# Phase_Shifting_Stage.net
KiCad netlist of a schematic drawn in Altium Designer
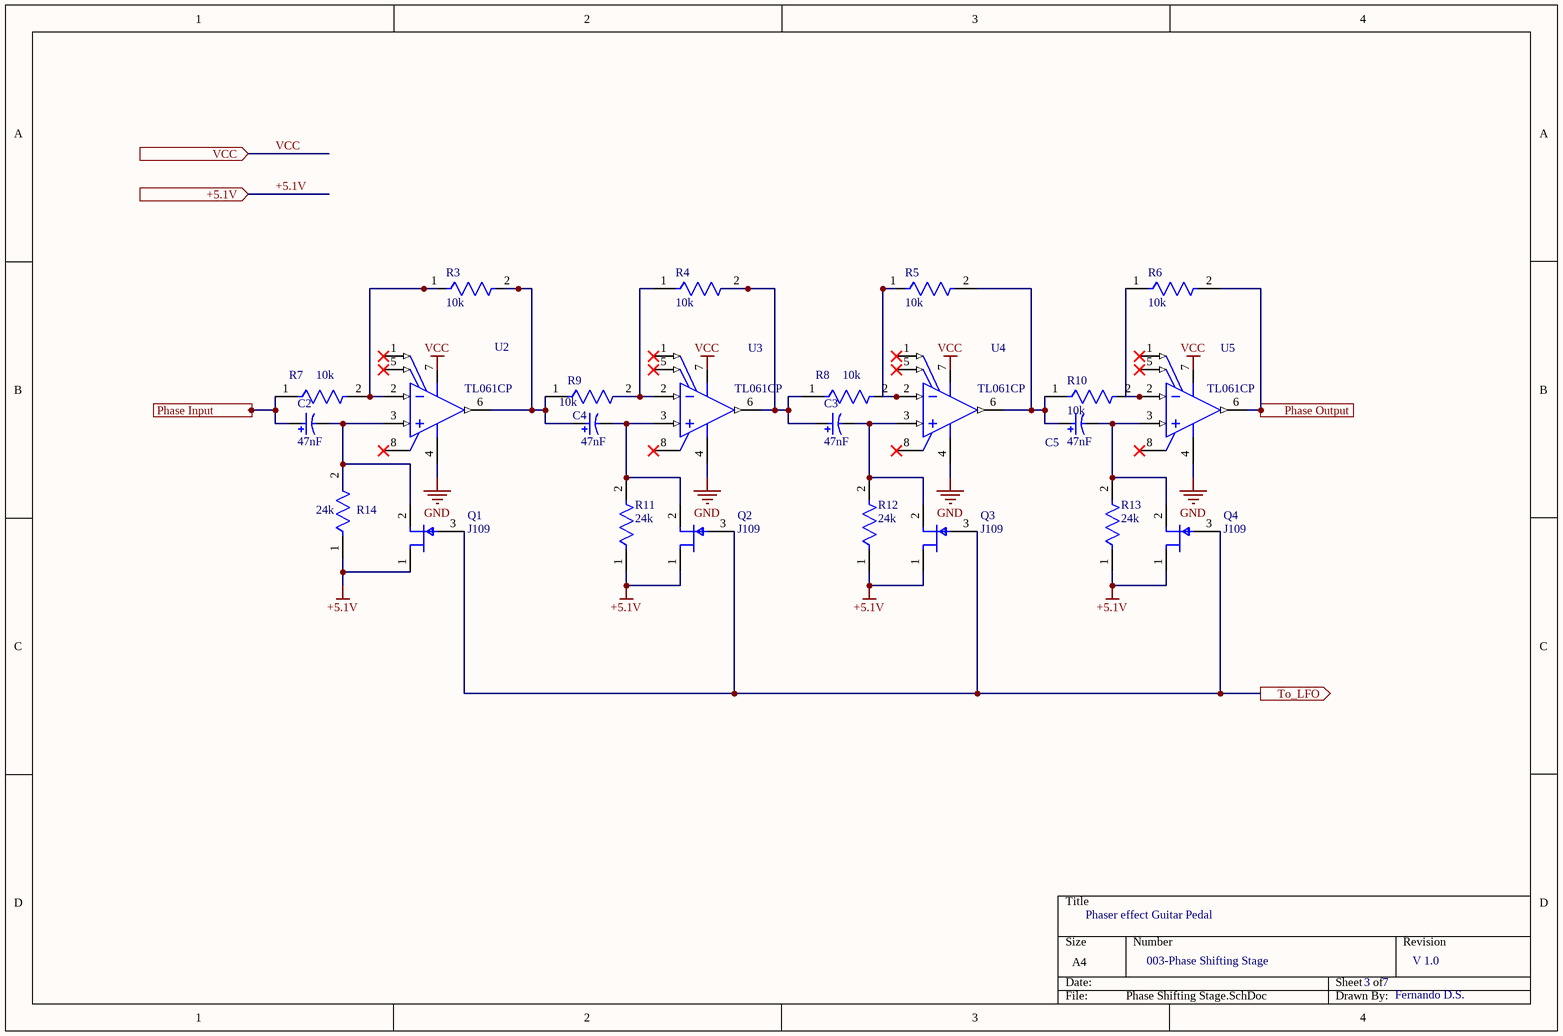
[diagram p0: Phase Shifting Stage.SchDoc]

(export (version "E")
  (design (tool "Eeschema 10.0.6"))
  (components
    (comp (ref "C2")
      (value "47nF")
      (footprint "NIC-PLF-10x13-2_V")
      (description "Aluminum Electrolytic Capacitor, 470 uF +/-20%, 10 V, -55 to 105 degC, 2-Pin THD, RoHS")
      (fields (field (name "MANUFACTURER") "Nichicon") (field (name "PARTNUMBER") "PLF1A471MDO1"))
      (libsource (lib "Altium Content Vault") (part "NIC-CAP-P-2"))
    )
    (comp (ref "C3")
      (value "47nF")
      (footprint "NIC-PLF-10x13-2_V")
      (description "Aluminum Electrolytic Capacitor, 470 uF +/-20%, 10 V, -55 to 105 degC, 2-Pin THD, RoHS")
      (fields (field (name "MANUFACTURER") "Nichicon") (field (name "PARTNUMBER") "PLF1A471MDO1"))
      (libsource (lib "Altium Content Vault") (part "NIC-CAP-P-2"))
    )
    (comp (ref "C4")
      (value "47nF")
      (footprint "NIC-PLF-10x13-2_V")
      (description "Aluminum Electrolytic Capacitor, 470 uF +/-20%, 10 V, -55 to 105 degC, 2-Pin THD, RoHS")
      (fields (field (name "MANUFACTURER") "Nichicon") (field (name "PARTNUMBER") "PLF1A471MDO1"))
      (libsource (lib "Altium Content Vault") (part "NIC-CAP-P-2"))
    )
    (comp (ref "C5")
      (value "47nF")
      (footprint "NIC-PLF-10x13-2_V")
      (description "Aluminum Electrolytic Capacitor, 470 uF +/-20%, 10 V, -55 to 105 degC, 2-Pin THD, RoHS")
      (fields (field (name "MANUFACTURER") "Nichicon") (field (name "PARTNUMBER") "PLF1A471MDO1"))
      (libsource (lib "Altium Content Vault") (part "NIC-CAP-P-2"))
    )
    (comp (ref "Q1")
      (value "J109")
      (footprint "FP-135AN-MFG")
      (description "J109 Fairchild Semiconductor J109JFET Transistor, Jfet, -25 V, 40 Ma, 6 V, TO-92, Jfet")
      (libsource (lib "Altium Content Vault") (part "14398f7355be6f33287877db3ee21c7"))
    )
    (comp (ref "Q2")
      (value "J109")
      (footprint "FP-135AN-MFG")
      (description "J109 Fairchild Semiconductor J109JFET Transistor, Jfet, -25 V, 40 Ma, 6 V, TO-92, Jfet")
      (libsource (lib "Altium Content Vault") (part "14398f7355be6f33287877db3ee21c7"))
    )
    (comp (ref "Q3")
      (value "J109")
      (footprint "FP-135AN-MFG")
      (description "J109 Fairchild Semiconductor J109JFET Transistor, Jfet, -25 V, 40 Ma, 6 V, TO-92, Jfet")
      (libsource (lib "Altium Content Vault") (part "14398f7355be6f33287877db3ee21c7"))
    )
    (comp (ref "Q4")
      (value "J109")
      (footprint "FP-135AN-MFG")
      (description "J109 Fairchild Semiconductor J109JFET Transistor, Jfet, -25 V, 40 Ma, 6 V, TO-92, Jfet")
      (libsource (lib "Altium Content Vault") (part "14398f7355be6f33287877db3ee21c7"))
    )
    (comp (ref "R3")
      (value "10k")
      (footprint "FP-MRS25-MFG")
      (fields (field (name "TOLERANCE") "1%"))
      (libsource (lib "Altium Content Vault") (part "1029c3af85768c4190bb7ad29bc67b5"))
    )
    (comp (ref "R4")
      (value "10k")
      (footprint "FP-MRS25-MFG")
      (fields (field (name "TOLERANCE") "1%"))
      (libsource (lib "Altium Content Vault") (part "1029c3af85768c4190bb7ad29bc67b5"))
    )
    (comp (ref "R5")
      (value "10k")
      (footprint "FP-MRS25-MFG")
      (fields (field (name "TOLERANCE") "1%"))
      (libsource (lib "Altium Content Vault") (part "1029c3af85768c4190bb7ad29bc67b5"))
    )
    (comp (ref "R6")
      (value "10k")
      (footprint "FP-MRS25-MFG")
      (fields (field (name "TOLERANCE") "1%"))
      (libsource (lib "Altium Content Vault") (part "1029c3af85768c4190bb7ad29bc67b5"))
    )
    (comp (ref "R7")
      (value "10k")
      (footprint "FP-MRS25-MFG")
      (fields (field (name "TOLERANCE") "1%"))
      (libsource (lib "Altium Content Vault") (part "1029c3af85768c4190bb7ad29bc67b5"))
    )
    (comp (ref "R8")
      (value "10k")
      (footprint "FP-MRS25-MFG")
      (fields (field (name "TOLERANCE") "1%"))
      (libsource (lib "Altium Content Vault") (part "1029c3af85768c4190bb7ad29bc67b5"))
    )
    (comp (ref "R9")
      (value "10k")
      (footprint "FP-MRS25-MFG")
      (fields (field (name "TOLERANCE") "1%"))
      (libsource (lib "Altium Content Vault") (part "1029c3af85768c4190bb7ad29bc67b5"))
    )
    (comp (ref "R10")
      (value "10k")
      (footprint "FP-MRS25-MFG")
      (fields (field (name "TOLERANCE") "1%"))
      (libsource (lib "Altium Content Vault") (part "1029c3af85768c4190bb7ad29bc67b5"))
    )
    (comp (ref "R11")
      (value "24k")
      (footprint "FP-MRS25-MFG")
      (fields (field (name "TOLERANCE") "1%"))
      (libsource (lib "Altium Content Vault") (part "1029c3af85768c4190bb7ad29bc67b5"))
    )
    (comp (ref "R12")
      (value "24k")
      (footprint "FP-MRS25-MFG")
      (fields (field (name "TOLERANCE") "1%"))
      (libsource (lib "Altium Content Vault") (part "1029c3af85768c4190bb7ad29bc67b5"))
    )
    (comp (ref "R13")
      (value "24k")
      (footprint "FP-MRS25-MFG")
      (fields (field (name "TOLERANCE") "1%"))
      (libsource (lib "Altium Content Vault") (part "1029c3af85768c4190bb7ad29bc67b5"))
    )
    (comp (ref "R14")
      (value "24k")
      (footprint "FP-MRS25-MFG")
      (fields (field (name "TOLERANCE") "1%"))
      (libsource (lib "Altium Content Vault") (part "1029c3af85768c4190bb7ad29bc67b5"))
    )
    (comp (ref "U2")
      (value "TL061CP")
      (footprint "P0008A")
      (fields (field (name "MANUFACTURER") "Texas Instruments"))
      (libsource (lib "Altium Content Vault") (part "TI-AMP-S5-2-8"))
    )
    (comp (ref "U3")
      (value "TL061CP")
      (footprint "P0008A")
      (fields (field (name "MANUFACTURER") "Texas Instruments"))
      (libsource (lib "Altium Content Vault") (part "TI-AMP-S5-2-8"))
    )
    (comp (ref "U4")
      (value "TL061CP")
      (footprint "P0008A")
      (fields (field (name "MANUFACTURER") "Texas Instruments"))
      (libsource (lib "Altium Content Vault") (part "TI-AMP-S5-2-8"))
    )
    (comp (ref "U5")
      (value "TL061CP")
      (footprint "P0008A")
      (fields (field (name "MANUFACTURER") "Texas Instruments"))
      (libsource (lib "Altium Content Vault") (part "TI-AMP-S5-2-8"))
    )
  )
  (nets
    (net (code "1") (name "+5.1V") (class "Default")
      (node (ref "Q1") (pin "1") (pinfunction "D_1") (pintype "passive"))
      (node (ref "Q2") (pin "1") (pinfunction "D_1") (pintype "passive"))
      (node (ref "Q3") (pin "1") (pinfunction "D_1") (pintype "passive"))
      (node (ref "Q4") (pin "1") (pinfunction "D_1") (pintype "passive"))
      (node (ref "R11") (pin "1") (pinfunction "1_1") (pintype "passive"))
      (node (ref "R12") (pin "1") (pinfunction "1_1") (pintype "passive"))
      (node (ref "R13") (pin "1") (pinfunction "1_1") (pintype "passive"))
      (node (ref "R14") (pin "1") (pinfunction "1_1") (pintype "passive"))
    )
    (net (code "2") (name "/Phase Input") (class "Default")
      (node (ref "C2") (pin "1") (pinfunction "1_1") (pintype "passive"))
      (node (ref "R7") (pin "1") (pinfunction "1_1") (pintype "passive"))
    )
    (net (code "3") (name "/Phase Output") (class "Default")
      (node (ref "R6") (pin "2") (pinfunction "2_2") (pintype "passive"))
      (node (ref "U5") (pin "6") (pinfunction "OUT_6") (pintype "output"))
    )
    (net (code "4") (name "/To_LFO") (class "Default")
      (node (ref "Q1") (pin "3") (pinfunction "G_3") (pintype "passive"))
      (node (ref "Q2") (pin "3") (pinfunction "G_3") (pintype "passive"))
      (node (ref "Q3") (pin "3") (pinfunction "G_3") (pintype "passive"))
      (node (ref "Q4") (pin "3") (pinfunction "G_3") (pintype "passive"))
    )
    (net (code "5") (name "GND") (class "Default")
      (node (ref "U2") (pin "4") (pinfunction "VCC-_4") (pintype "power_in"))
      (node (ref "U3") (pin "4") (pinfunction "VCC-_4") (pintype "power_in"))
      (node (ref "U4") (pin "4") (pinfunction "VCC-_4") (pintype "power_in"))
      (node (ref "U5") (pin "4") (pinfunction "VCC-_4") (pintype "power_in"))
    )
    (net (code "6") (name "Net-(Q1-S)") (class "Default")
      (node (ref "C2") (pin "2") (pinfunction "2_2") (pintype "passive"))
      (node (ref "Q1") (pin "2") (pinfunction "S_2") (pintype "passive"))
      (node (ref "R14") (pin "2") (pinfunction "2_2") (pintype "passive"))
      (node (ref "U2") (pin "3") (pinfunction "IN+_3") (pintype "input"))
    )
    (net (code "7") (name "Net-(Q2-S)") (class "Default")
      (node (ref "C4") (pin "2") (pinfunction "2_2") (pintype "passive"))
      (node (ref "Q2") (pin "2") (pinfunction "S_2") (pintype "passive"))
      (node (ref "R11") (pin "2") (pinfunction "2_2") (pintype "passive"))
      (node (ref "U3") (pin "3") (pinfunction "IN+_3") (pintype "input"))
    )
    (net (code "8") (name "Net-(Q3-S)") (class "Default")
      (node (ref "C3") (pin "2") (pinfunction "2_2") (pintype "passive"))
      (node (ref "Q3") (pin "2") (pinfunction "S_2") (pintype "passive"))
      (node (ref "R12") (pin "2") (pinfunction "2_2") (pintype "passive"))
      (node (ref "U4") (pin "3") (pinfunction "IN+_3") (pintype "input"))
    )
    (net (code "9") (name "Net-(Q4-S)") (class "Default")
      (node (ref "C5") (pin "2") (pinfunction "2_2") (pintype "passive"))
      (node (ref "Q4") (pin "2") (pinfunction "S_2") (pintype "passive"))
      (node (ref "R13") (pin "2") (pinfunction "2_2") (pintype "passive"))
      (node (ref "U5") (pin "3") (pinfunction "IN+_3") (pintype "input"))
    )
    (net (code "10") (name "Net-(U2-IN-)") (class "Default")
      (node (ref "R3") (pin "1") (pinfunction "1_1") (pintype "passive"))
      (node (ref "R7") (pin "2") (pinfunction "2_2") (pintype "passive"))
      (node (ref "U2") (pin "2") (pinfunction "IN-_2") (pintype "input"))
    )
    (net (code "11") (name "Net-(U2-OUT)") (class "Default")
      (node (ref "C4") (pin "1") (pinfunction "1_1") (pintype "passive"))
      (node (ref "R3") (pin "2") (pinfunction "2_2") (pintype "passive"))
      (node (ref "R9") (pin "1") (pinfunction "1_1") (pintype "passive"))
      (node (ref "U2") (pin "6") (pinfunction "OUT_6") (pintype "output"))
    )
    (net (code "12") (name "Net-(U3-IN-)") (class "Default")
      (node (ref "R4") (pin "1") (pinfunction "1_1") (pintype "passive"))
      (node (ref "R9") (pin "2") (pinfunction "2_2") (pintype "passive"))
      (node (ref "U3") (pin "2") (pinfunction "IN-_2") (pintype "input"))
    )
    (net (code "13") (name "Net-(U3-OUT)") (class "Default")
      (node (ref "C3") (pin "1") (pinfunction "1_1") (pintype "passive"))
      (node (ref "R4") (pin "2") (pinfunction "2_2") (pintype "passive"))
      (node (ref "R8") (pin "1") (pinfunction "1_1") (pintype "passive"))
      (node (ref "U3") (pin "6") (pinfunction "OUT_6") (pintype "output"))
    )
    (net (code "14") (name "Net-(U4-IN-)") (class "Default")
      (node (ref "R5") (pin "1") (pinfunction "1_1") (pintype "passive"))
      (node (ref "R8") (pin "2") (pinfunction "2_2") (pintype "passive"))
      (node (ref "U4") (pin "2") (pinfunction "IN-_2") (pintype "input"))
    )
    (net (code "15") (name "Net-(U4-OUT)") (class "Default")
      (node (ref "C5") (pin "1") (pinfunction "1_1") (pintype "passive"))
      (node (ref "R10") (pin "1") (pinfunction "1_1") (pintype "passive"))
      (node (ref "R5") (pin "2") (pinfunction "2_2") (pintype "passive"))
      (node (ref "U4") (pin "6") (pinfunction "OUT_6") (pintype "output"))
    )
    (net (code "16") (name "Net-(U5-IN-)") (class "Default")
      (node (ref "R10") (pin "2") (pinfunction "2_2") (pintype "passive"))
      (node (ref "R6") (pin "1") (pinfunction "1_1") (pintype "passive"))
      (node (ref "U5") (pin "2") (pinfunction "IN-_2") (pintype "input"))
    )
    (net (code "18") (name "unconnected-(U2-NC-Pad8)") (class "Default")
      (node (ref "U2") (pin "8") (pinfunction "NC_8") (pintype "passive+no_connect"))
    )
    (net (code "19") (name "unconnected-(U2-OFFSET_N1-Pad1)") (class "Default")
      (node (ref "U2") (pin "1") (pinfunction "OFFSET_N1_1") (pintype "input+no_connect"))
    )
    (net (code "20") (name "unconnected-(U2-OFFSET_N2-Pad5)") (class "Default")
      (node (ref "U2") (pin "5") (pinfunction "OFFSET_N2_5") (pintype "input+no_connect"))
    )
    (net (code "21") (name "unconnected-(U2-VCC+-Pad7)") (class "Default")
      (node (ref "U2") (pin "7") (pinfunction "VCC+_7") (pintype "power_in"))
    )
    (net (code "22") (name "unconnected-(U3-NC-Pad8)") (class "Default")
      (node (ref "U3") (pin "8") (pinfunction "NC_8") (pintype "passive+no_connect"))
    )
    (net (code "23") (name "unconnected-(U3-OFFSET_N1-Pad1)") (class "Default")
      (node (ref "U3") (pin "1") (pinfunction "OFFSET_N1_1") (pintype "input+no_connect"))
    )
    (net (code "24") (name "unconnected-(U3-OFFSET_N2-Pad5)") (class "Default")
      (node (ref "U3") (pin "5") (pinfunction "OFFSET_N2_5") (pintype "input+no_connect"))
    )
    (net (code "25") (name "unconnected-(U3-VCC+-Pad7)") (class "Default")
      (node (ref "U3") (pin "7") (pinfunction "VCC+_7") (pintype "power_in"))
    )
    (net (code "26") (name "unconnected-(U4-NC-Pad8)") (class "Default")
      (node (ref "U4") (pin "8") (pinfunction "NC_8") (pintype "passive+no_connect"))
    )
    (net (code "27") (name "unconnected-(U4-OFFSET_N1-Pad1)") (class "Default")
      (node (ref "U4") (pin "1") (pinfunction "OFFSET_N1_1") (pintype "input+no_connect"))
    )
    (net (code "28") (name "unconnected-(U4-OFFSET_N2-Pad5)") (class "Default")
      (node (ref "U4") (pin "5") (pinfunction "OFFSET_N2_5") (pintype "input+no_connect"))
    )
    (net (code "29") (name "unconnected-(U4-VCC+-Pad7)") (class "Default")
      (node (ref "U4") (pin "7") (pinfunction "VCC+_7") (pintype "power_in"))
    )
    (net (code "30") (name "unconnected-(U5-NC-Pad8)") (class "Default")
      (node (ref "U5") (pin "8") (pinfunction "NC_8") (pintype "passive+no_connect"))
    )
    (net (code "31") (name "unconnected-(U5-OFFSET_N1-Pad1)") (class "Default")
      (node (ref "U5") (pin "1") (pinfunction "OFFSET_N1_1") (pintype "input+no_connect"))
    )
    (net (code "32") (name "unconnected-(U5-OFFSET_N2-Pad5)") (class "Default")
      (node (ref "U5") (pin "5") (pinfunction "OFFSET_N2_5") (pintype "input+no_connect"))
    )
    (net (code "33") (name "unconnected-(U5-VCC+-Pad7)") (class "Default")
      (node (ref "U5") (pin "7") (pinfunction "VCC+_7") (pintype "power_in"))
    )
  )
)
